# PIN_1_1.net
KiCad netlist of a schematic drawn in EAGLE
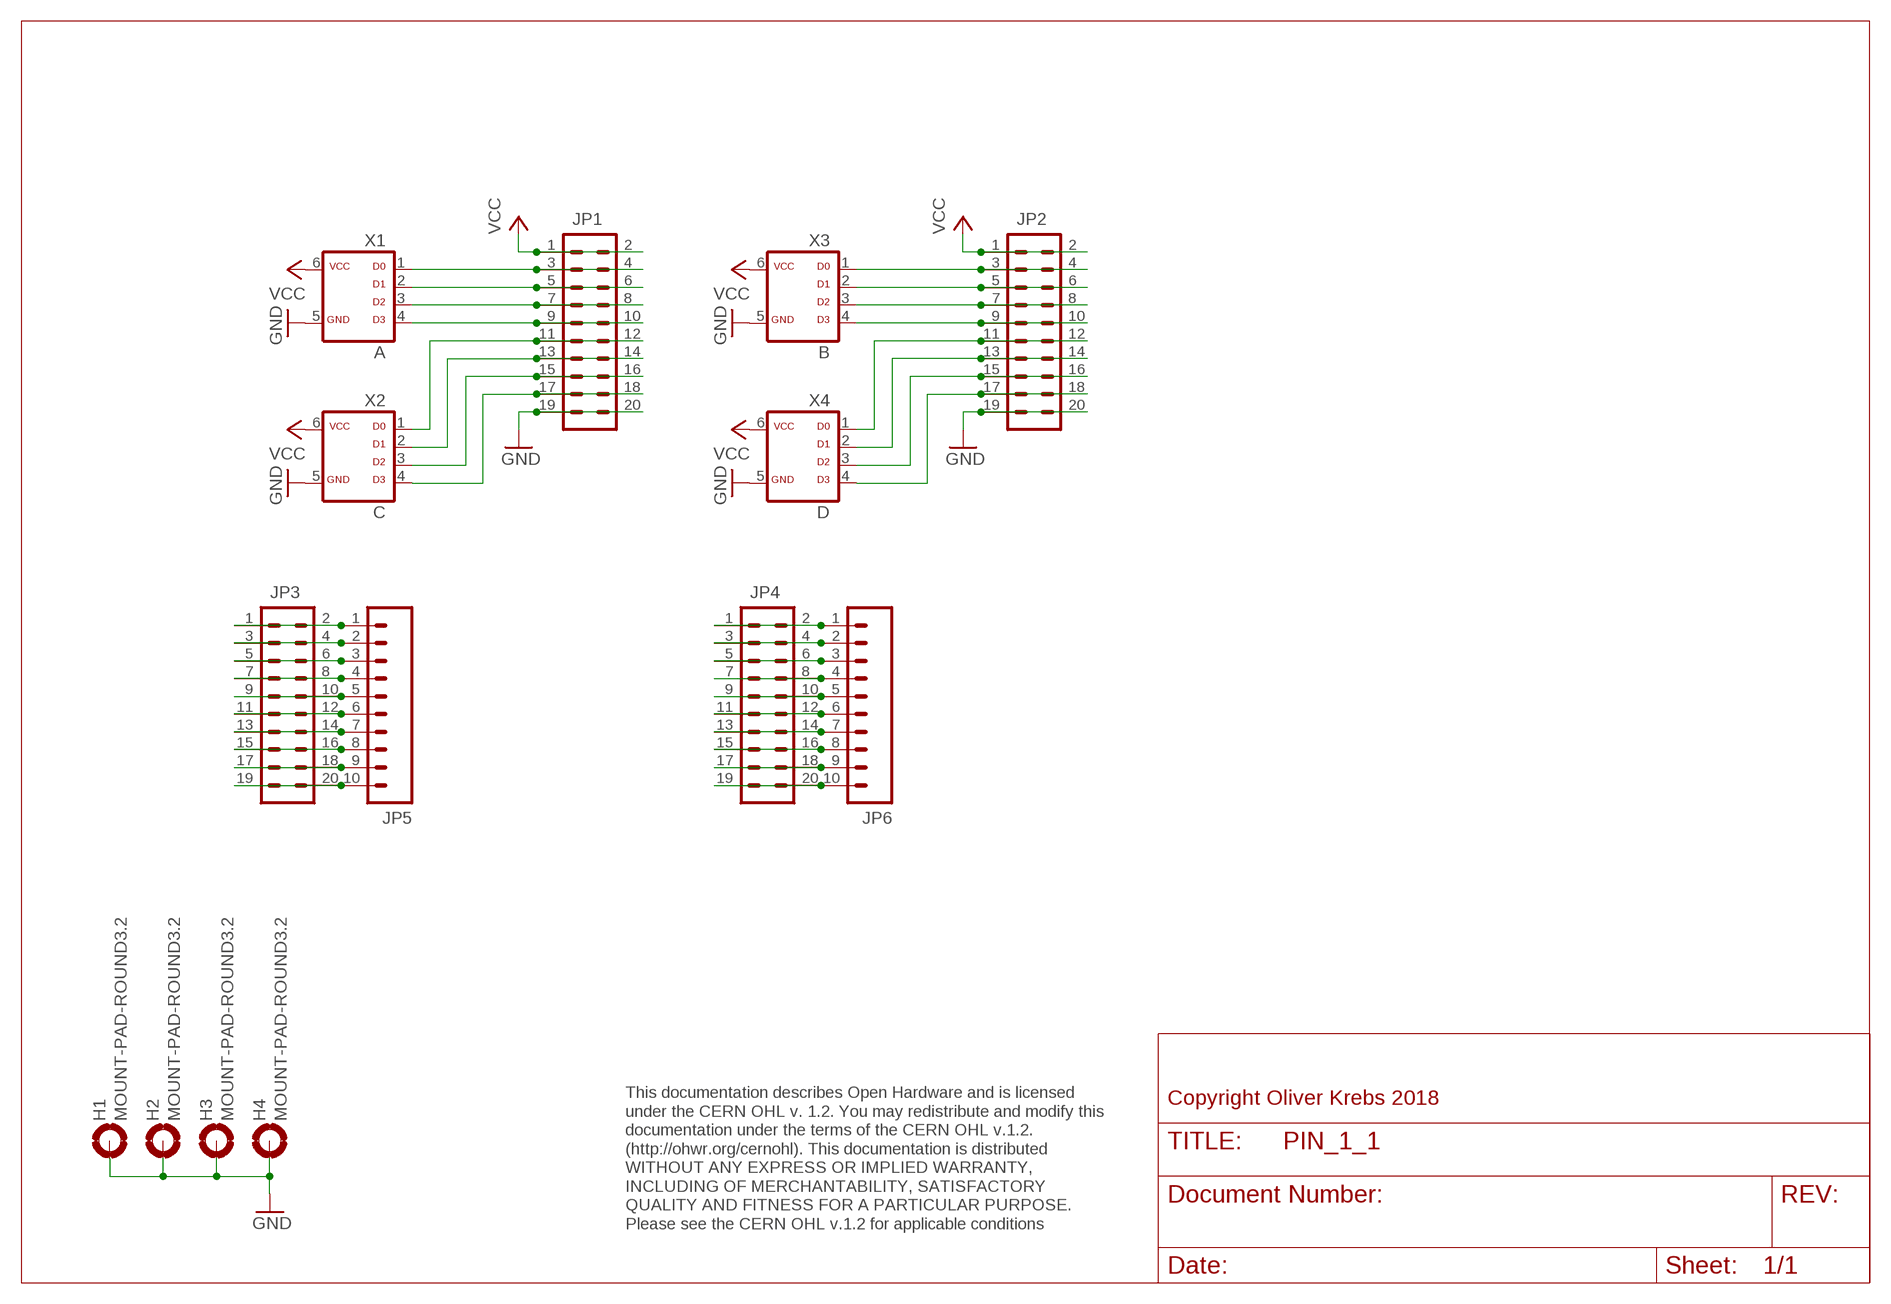
[diagram p0: schematic, sheet 1]

(export (version "E")
  (design (tool "Eeschema 10.0.6"))
  (components
    (comp (ref "H1")
      (value "MOUNT-PAD-ROUND3.2")
      (footprint "eagle-import:3,2-PAD")
      (libsource (lib "eagle-import") (part "MOUNT-PAD-ROUND3.2"))
    )
    (comp (ref "H2")
      (value "MOUNT-PAD-ROUND3.2")
      (footprint "eagle-import:3,2-PAD")
      (libsource (lib "eagle-import") (part "MOUNT-PAD-ROUND3.2"))
    )
    (comp (ref "H3")
      (value "MOUNT-PAD-ROUND3.2")
      (footprint "eagle-import:3,2-PAD")
      (libsource (lib "eagle-import") (part "MOUNT-PAD-ROUND3.2"))
    )
    (comp (ref "H4")
      (value "MOUNT-PAD-ROUND3.2")
      (footprint "eagle-import:3,2-PAD")
      (libsource (lib "eagle-import") (part "MOUNT-PAD-ROUND3.2"))
    )
    (comp (ref "JP1")
      (value "M10X2")
      (footprint "eagle-import:2X10")
      (libsource (lib "eagle-import") (part "M10X2"))
    )
    (comp (ref "JP2")
      (value "M10X2")
      (footprint "eagle-import:2X10")
      (libsource (lib "eagle-import") (part "M10X2"))
    )
    (comp (ref "JP3")
      (value "M10X2")
      (footprint "eagle-import:2X10")
      (libsource (lib "eagle-import") (part "M10X2"))
    )
    (comp (ref "JP4")
      (value "M10X2")
      (footprint "eagle-import:2X10")
      (libsource (lib "eagle-import") (part "M10X2"))
    )
    (comp (ref "JP5")
      (value "M10SILK_FEMALE_PTH")
      (footprint "eagle-import:1X10")
      (libsource (lib "eagle-import") (part "M10SILK_FEMALE_PTH"))
    )
    (comp (ref "JP6")
      (value "M10SILK_FEMALE_PTH")
      (footprint "eagle-import:1X10")
      (libsource (lib "eagle-import") (part "M10SILK_FEMALE_PTH"))
    )
    (comp (ref "X1")
      (value "A")
      (footprint "eagle-import:ML-6")
      (libsource (lib "eagle-import") (part "ML6D"))
    )
    (comp (ref "X2")
      (value "C")
      (footprint "eagle-import:ML-6")
      (libsource (lib "eagle-import") (part "ML6D"))
    )
    (comp (ref "X3")
      (value "B")
      (footprint "eagle-import:ML-6")
      (libsource (lib "eagle-import") (part "ML6D"))
    )
    (comp (ref "X4")
      (value "D")
      (footprint "eagle-import:ML-6")
      (libsource (lib "eagle-import") (part "ML6D"))
    )
  )
  (nets
    (net (code "1") (name "GND") (class "Default")
      (node (ref "H1") (pin "B3,2") (pinfunction "MOUNT_B3,2") (pintype "passive"))
      (node (ref "H2") (pin "B3,2") (pinfunction "MOUNT_B3,2") (pintype "passive"))
      (node (ref "H3") (pin "B3,2") (pinfunction "MOUNT_B3,2") (pintype "passive"))
      (node (ref "H4") (pin "B3,2") (pinfunction "MOUNT_B3,2") (pintype "passive"))
      (node (ref "JP1") (pin "19") (pinfunction "19_19") (pintype "passive"))
      (node (ref "JP1") (pin "20") (pinfunction "20_20") (pintype "passive"))
      (node (ref "JP2") (pin "19") (pinfunction "19_19") (pintype "passive"))
      (node (ref "JP2") (pin "20") (pinfunction "20_20") (pintype "passive"))
      (node (ref "X1") (pin "5") (pinfunction "5_5") (pintype "passive"))
      (node (ref "X2") (pin "5") (pinfunction "5_5") (pintype "passive"))
      (node (ref "X3") (pin "5") (pinfunction "5_5") (pintype "passive"))
      (node (ref "X4") (pin "5") (pinfunction "5_5") (pintype "passive"))
    )
    (net (code "2") (name "Net-(JP1-Pad3)") (class "Default")
      (node (ref "JP1") (pin "3") (pinfunction "3_3") (pintype "passive"))
      (node (ref "JP1") (pin "4") (pinfunction "4_4") (pintype "passive"))
      (node (ref "X1") (pin "1") (pinfunction "1_1") (pintype "passive"))
    )
    (net (code "3") (name "Net-(JP1-Pad5)") (class "Default")
      (node (ref "JP1") (pin "5") (pinfunction "5_5") (pintype "passive"))
      (node (ref "JP1") (pin "6") (pinfunction "6_6") (pintype "passive"))
      (node (ref "X1") (pin "2") (pinfunction "2_2") (pintype "passive"))
    )
    (net (code "4") (name "Net-(JP1-Pad7)") (class "Default")
      (node (ref "JP1") (pin "7") (pinfunction "7_7") (pintype "passive"))
      (node (ref "JP1") (pin "8") (pinfunction "8_8") (pintype "passive"))
      (node (ref "X1") (pin "3") (pinfunction "3_3") (pintype "passive"))
    )
    (net (code "5") (name "Net-(JP1-Pad10)") (class "Default")
      (node (ref "JP1") (pin "10") (pinfunction "10_10") (pintype "passive"))
      (node (ref "JP1") (pin "9") (pinfunction "9_9") (pintype "passive"))
      (node (ref "X1") (pin "4") (pinfunction "4_4") (pintype "passive"))
    )
    (net (code "6") (name "Net-(JP1-Pad11)") (class "Default")
      (node (ref "JP1") (pin "11") (pinfunction "11_11") (pintype "passive"))
      (node (ref "JP1") (pin "12") (pinfunction "12_12") (pintype "passive"))
      (node (ref "X2") (pin "1") (pinfunction "1_1") (pintype "passive"))
    )
    (net (code "7") (name "Net-(JP1-Pad13)") (class "Default")
      (node (ref "JP1") (pin "13") (pinfunction "13_13") (pintype "passive"))
      (node (ref "JP1") (pin "14") (pinfunction "14_14") (pintype "passive"))
      (node (ref "X2") (pin "2") (pinfunction "2_2") (pintype "passive"))
    )
    (net (code "8") (name "Net-(JP1-Pad15)") (class "Default")
      (node (ref "JP1") (pin "15") (pinfunction "15_15") (pintype "passive"))
      (node (ref "JP1") (pin "16") (pinfunction "16_16") (pintype "passive"))
      (node (ref "X2") (pin "3") (pinfunction "3_3") (pintype "passive"))
    )
    (net (code "9") (name "Net-(JP1-Pad17)") (class "Default")
      (node (ref "JP1") (pin "17") (pinfunction "17_17") (pintype "passive"))
      (node (ref "JP1") (pin "18") (pinfunction "18_18") (pintype "passive"))
      (node (ref "X2") (pin "4") (pinfunction "4_4") (pintype "passive"))
    )
    (net (code "10") (name "Net-(JP2-Pad3)") (class "Default")
      (node (ref "JP2") (pin "3") (pinfunction "3_3") (pintype "passive"))
      (node (ref "JP2") (pin "4") (pinfunction "4_4") (pintype "passive"))
      (node (ref "X3") (pin "1") (pinfunction "1_1") (pintype "passive"))
    )
    (net (code "11") (name "Net-(JP2-Pad5)") (class "Default")
      (node (ref "JP2") (pin "5") (pinfunction "5_5") (pintype "passive"))
      (node (ref "JP2") (pin "6") (pinfunction "6_6") (pintype "passive"))
      (node (ref "X3") (pin "2") (pinfunction "2_2") (pintype "passive"))
    )
    (net (code "12") (name "Net-(JP2-Pad7)") (class "Default")
      (node (ref "JP2") (pin "7") (pinfunction "7_7") (pintype "passive"))
      (node (ref "JP2") (pin "8") (pinfunction "8_8") (pintype "passive"))
      (node (ref "X3") (pin "3") (pinfunction "3_3") (pintype "passive"))
    )
    (net (code "13") (name "Net-(JP2-Pad10)") (class "Default")
      (node (ref "JP2") (pin "10") (pinfunction "10_10") (pintype "passive"))
      (node (ref "JP2") (pin "9") (pinfunction "9_9") (pintype "passive"))
      (node (ref "X3") (pin "4") (pinfunction "4_4") (pintype "passive"))
    )
    (net (code "14") (name "Net-(JP2-Pad11)") (class "Default")
      (node (ref "JP2") (pin "11") (pinfunction "11_11") (pintype "passive"))
      (node (ref "JP2") (pin "12") (pinfunction "12_12") (pintype "passive"))
      (node (ref "X4") (pin "1") (pinfunction "1_1") (pintype "passive"))
    )
    (net (code "15") (name "Net-(JP2-Pad13)") (class "Default")
      (node (ref "JP2") (pin "13") (pinfunction "13_13") (pintype "passive"))
      (node (ref "JP2") (pin "14") (pinfunction "14_14") (pintype "passive"))
      (node (ref "X4") (pin "2") (pinfunction "2_2") (pintype "passive"))
    )
    (net (code "16") (name "Net-(JP2-Pad15)") (class "Default")
      (node (ref "JP2") (pin "15") (pinfunction "15_15") (pintype "passive"))
      (node (ref "JP2") (pin "16") (pinfunction "16_16") (pintype "passive"))
      (node (ref "X4") (pin "3") (pinfunction "3_3") (pintype "passive"))
    )
    (net (code "17") (name "Net-(JP2-Pad17)") (class "Default")
      (node (ref "JP2") (pin "17") (pinfunction "17_17") (pintype "passive"))
      (node (ref "JP2") (pin "18") (pinfunction "18_18") (pintype "passive"))
      (node (ref "X4") (pin "4") (pinfunction "4_4") (pintype "passive"))
    )
    (net (code "18") (name "Net-(JP3-Pad1)") (class "Default")
      (node (ref "JP3") (pin "1") (pinfunction "1_1") (pintype "passive"))
      (node (ref "JP3") (pin "2") (pinfunction "2_2") (pintype "passive"))
      (node (ref "JP5") (pin "1") (pinfunction "1_1") (pintype "passive"))
    )
    (net (code "19") (name "Net-(JP3-Pad3)") (class "Default")
      (node (ref "JP3") (pin "3") (pinfunction "3_3") (pintype "passive"))
      (node (ref "JP3") (pin "4") (pinfunction "4_4") (pintype "passive"))
      (node (ref "JP5") (pin "2") (pinfunction "2_2") (pintype "passive"))
    )
    (net (code "20") (name "Net-(JP3-Pad5)") (class "Default")
      (node (ref "JP3") (pin "5") (pinfunction "5_5") (pintype "passive"))
      (node (ref "JP3") (pin "6") (pinfunction "6_6") (pintype "passive"))
      (node (ref "JP5") (pin "3") (pinfunction "3_3") (pintype "passive"))
    )
    (net (code "21") (name "Net-(JP3-Pad7)") (class "Default")
      (node (ref "JP3") (pin "7") (pinfunction "7_7") (pintype "passive"))
      (node (ref "JP3") (pin "8") (pinfunction "8_8") (pintype "passive"))
      (node (ref "JP5") (pin "4") (pinfunction "4_4") (pintype "passive"))
    )
    (net (code "22") (name "Net-(JP3-Pad10)") (class "Default")
      (node (ref "JP3") (pin "10") (pinfunction "10_10") (pintype "passive"))
      (node (ref "JP3") (pin "9") (pinfunction "9_9") (pintype "passive"))
      (node (ref "JP5") (pin "5") (pinfunction "5_5") (pintype "passive"))
    )
    (net (code "23") (name "Net-(JP3-Pad11)") (class "Default")
      (node (ref "JP3") (pin "11") (pinfunction "11_11") (pintype "passive"))
      (node (ref "JP3") (pin "12") (pinfunction "12_12") (pintype "passive"))
      (node (ref "JP5") (pin "6") (pinfunction "6_6") (pintype "passive"))
    )
    (net (code "24") (name "Net-(JP3-Pad13)") (class "Default")
      (node (ref "JP3") (pin "13") (pinfunction "13_13") (pintype "passive"))
      (node (ref "JP3") (pin "14") (pinfunction "14_14") (pintype "passive"))
      (node (ref "JP5") (pin "7") (pinfunction "7_7") (pintype "passive"))
    )
    (net (code "25") (name "Net-(JP3-Pad15)") (class "Default")
      (node (ref "JP3") (pin "15") (pinfunction "15_15") (pintype "passive"))
      (node (ref "JP3") (pin "16") (pinfunction "16_16") (pintype "passive"))
      (node (ref "JP5") (pin "8") (pinfunction "8_8") (pintype "passive"))
    )
    (net (code "26") (name "Net-(JP3-Pad17)") (class "Default")
      (node (ref "JP3") (pin "17") (pinfunction "17_17") (pintype "passive"))
      (node (ref "JP3") (pin "18") (pinfunction "18_18") (pintype "passive"))
      (node (ref "JP5") (pin "9") (pinfunction "9_9") (pintype "passive"))
    )
    (net (code "27") (name "Net-(JP3-Pad19)") (class "Default")
      (node (ref "JP3") (pin "19") (pinfunction "19_19") (pintype "passive"))
      (node (ref "JP3") (pin "20") (pinfunction "20_20") (pintype "passive"))
      (node (ref "JP5") (pin "10") (pinfunction "10_10") (pintype "passive"))
    )
    (net (code "28") (name "Net-(JP4-Pad1)") (class "Default")
      (node (ref "JP4") (pin "1") (pinfunction "1_1") (pintype "passive"))
      (node (ref "JP4") (pin "2") (pinfunction "2_2") (pintype "passive"))
      (node (ref "JP6") (pin "1") (pinfunction "1_1") (pintype "passive"))
    )
    (net (code "29") (name "Net-(JP4-Pad3)") (class "Default")
      (node (ref "JP4") (pin "3") (pinfunction "3_3") (pintype "passive"))
      (node (ref "JP4") (pin "4") (pinfunction "4_4") (pintype "passive"))
      (node (ref "JP6") (pin "2") (pinfunction "2_2") (pintype "passive"))
    )
    (net (code "30") (name "Net-(JP4-Pad5)") (class "Default")
      (node (ref "JP4") (pin "5") (pinfunction "5_5") (pintype "passive"))
      (node (ref "JP4") (pin "6") (pinfunction "6_6") (pintype "passive"))
      (node (ref "JP6") (pin "3") (pinfunction "3_3") (pintype "passive"))
    )
    (net (code "31") (name "Net-(JP4-Pad7)") (class "Default")
      (node (ref "JP4") (pin "7") (pinfunction "7_7") (pintype "passive"))
      (node (ref "JP4") (pin "8") (pinfunction "8_8") (pintype "passive"))
      (node (ref "JP6") (pin "4") (pinfunction "4_4") (pintype "passive"))
    )
    (net (code "32") (name "Net-(JP4-Pad10)") (class "Default")
      (node (ref "JP4") (pin "10") (pinfunction "10_10") (pintype "passive"))
      (node (ref "JP4") (pin "9") (pinfunction "9_9") (pintype "passive"))
      (node (ref "JP6") (pin "5") (pinfunction "5_5") (pintype "passive"))
    )
    (net (code "33") (name "Net-(JP4-Pad11)") (class "Default")
      (node (ref "JP4") (pin "11") (pinfunction "11_11") (pintype "passive"))
      (node (ref "JP4") (pin "12") (pinfunction "12_12") (pintype "passive"))
      (node (ref "JP6") (pin "6") (pinfunction "6_6") (pintype "passive"))
    )
    (net (code "34") (name "Net-(JP4-Pad13)") (class "Default")
      (node (ref "JP4") (pin "13") (pinfunction "13_13") (pintype "passive"))
      (node (ref "JP4") (pin "14") (pinfunction "14_14") (pintype "passive"))
      (node (ref "JP6") (pin "7") (pinfunction "7_7") (pintype "passive"))
    )
    (net (code "35") (name "Net-(JP4-Pad15)") (class "Default")
      (node (ref "JP4") (pin "15") (pinfunction "15_15") (pintype "passive"))
      (node (ref "JP4") (pin "16") (pinfunction "16_16") (pintype "passive"))
      (node (ref "JP6") (pin "8") (pinfunction "8_8") (pintype "passive"))
    )
    (net (code "36") (name "Net-(JP4-Pad17)") (class "Default")
      (node (ref "JP4") (pin "17") (pinfunction "17_17") (pintype "passive"))
      (node (ref "JP4") (pin "18") (pinfunction "18_18") (pintype "passive"))
      (node (ref "JP6") (pin "9") (pinfunction "9_9") (pintype "passive"))
    )
    (net (code "37") (name "Net-(JP4-Pad19)") (class "Default")
      (node (ref "JP4") (pin "19") (pinfunction "19_19") (pintype "passive"))
      (node (ref "JP4") (pin "20") (pinfunction "20_20") (pintype "passive"))
      (node (ref "JP6") (pin "10") (pinfunction "10_10") (pintype "passive"))
    )
    (net (code "38") (name "VCC") (class "Default")
      (node (ref "JP1") (pin "1") (pinfunction "1_1") (pintype "passive"))
      (node (ref "JP1") (pin "2") (pinfunction "2_2") (pintype "passive"))
      (node (ref "JP2") (pin "1") (pinfunction "1_1") (pintype "passive"))
      (node (ref "JP2") (pin "2") (pinfunction "2_2") (pintype "passive"))
      (node (ref "X1") (pin "6") (pinfunction "6_6") (pintype "passive"))
      (node (ref "X2") (pin "6") (pinfunction "6_6") (pintype "passive"))
      (node (ref "X3") (pin "6") (pinfunction "6_6") (pintype "passive"))
      (node (ref "X4") (pin "6") (pinfunction "6_6") (pintype "passive"))
    )
  )
)
